# v5-pi.net
KiCad netlist of a schematic drawn in EAGLE
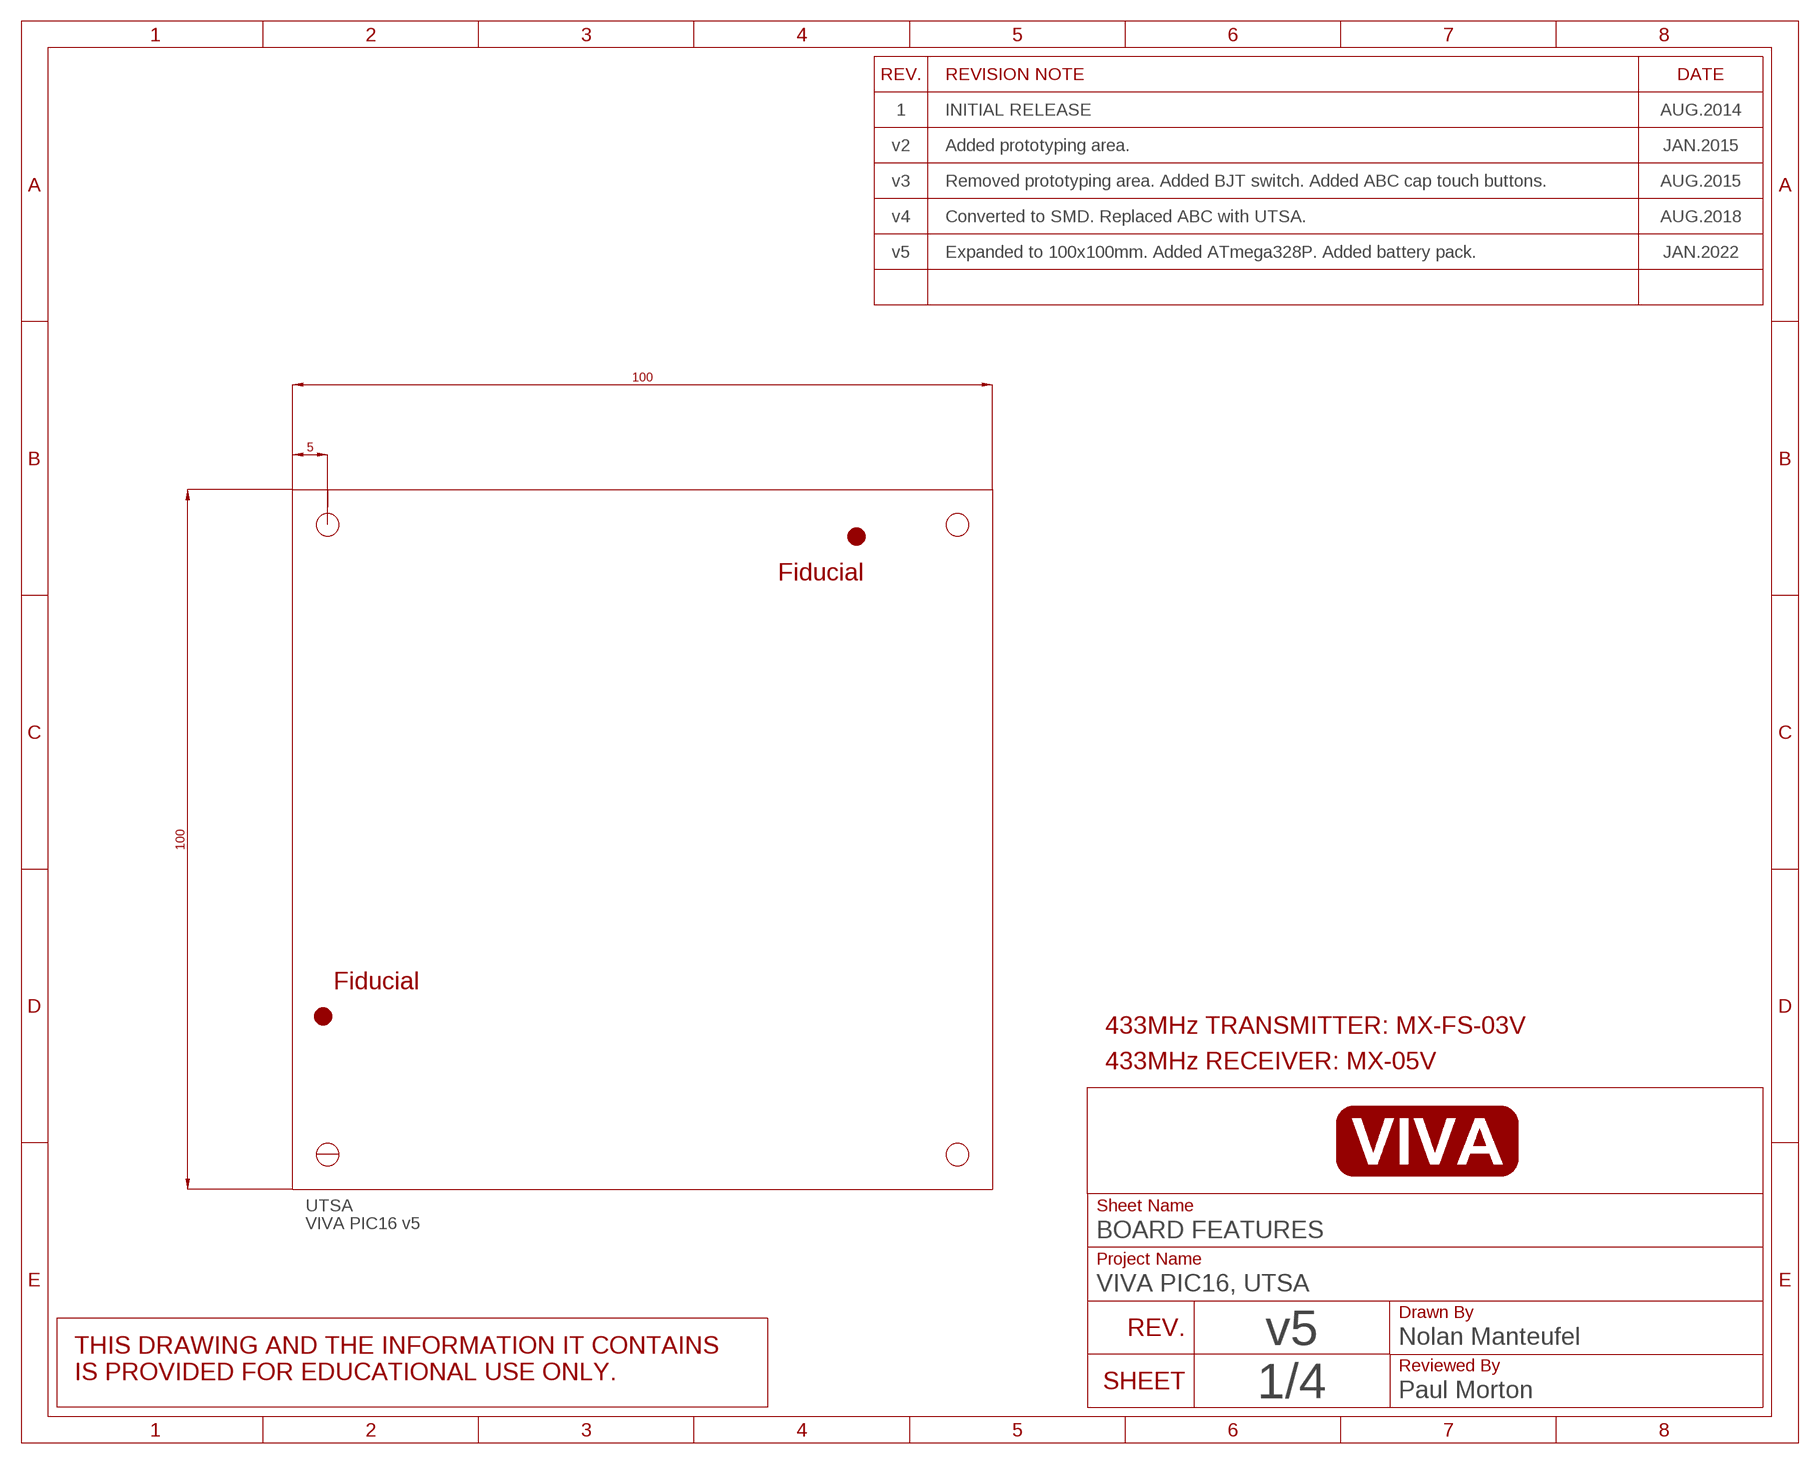
[diagram p0: schematic, sheet 1]
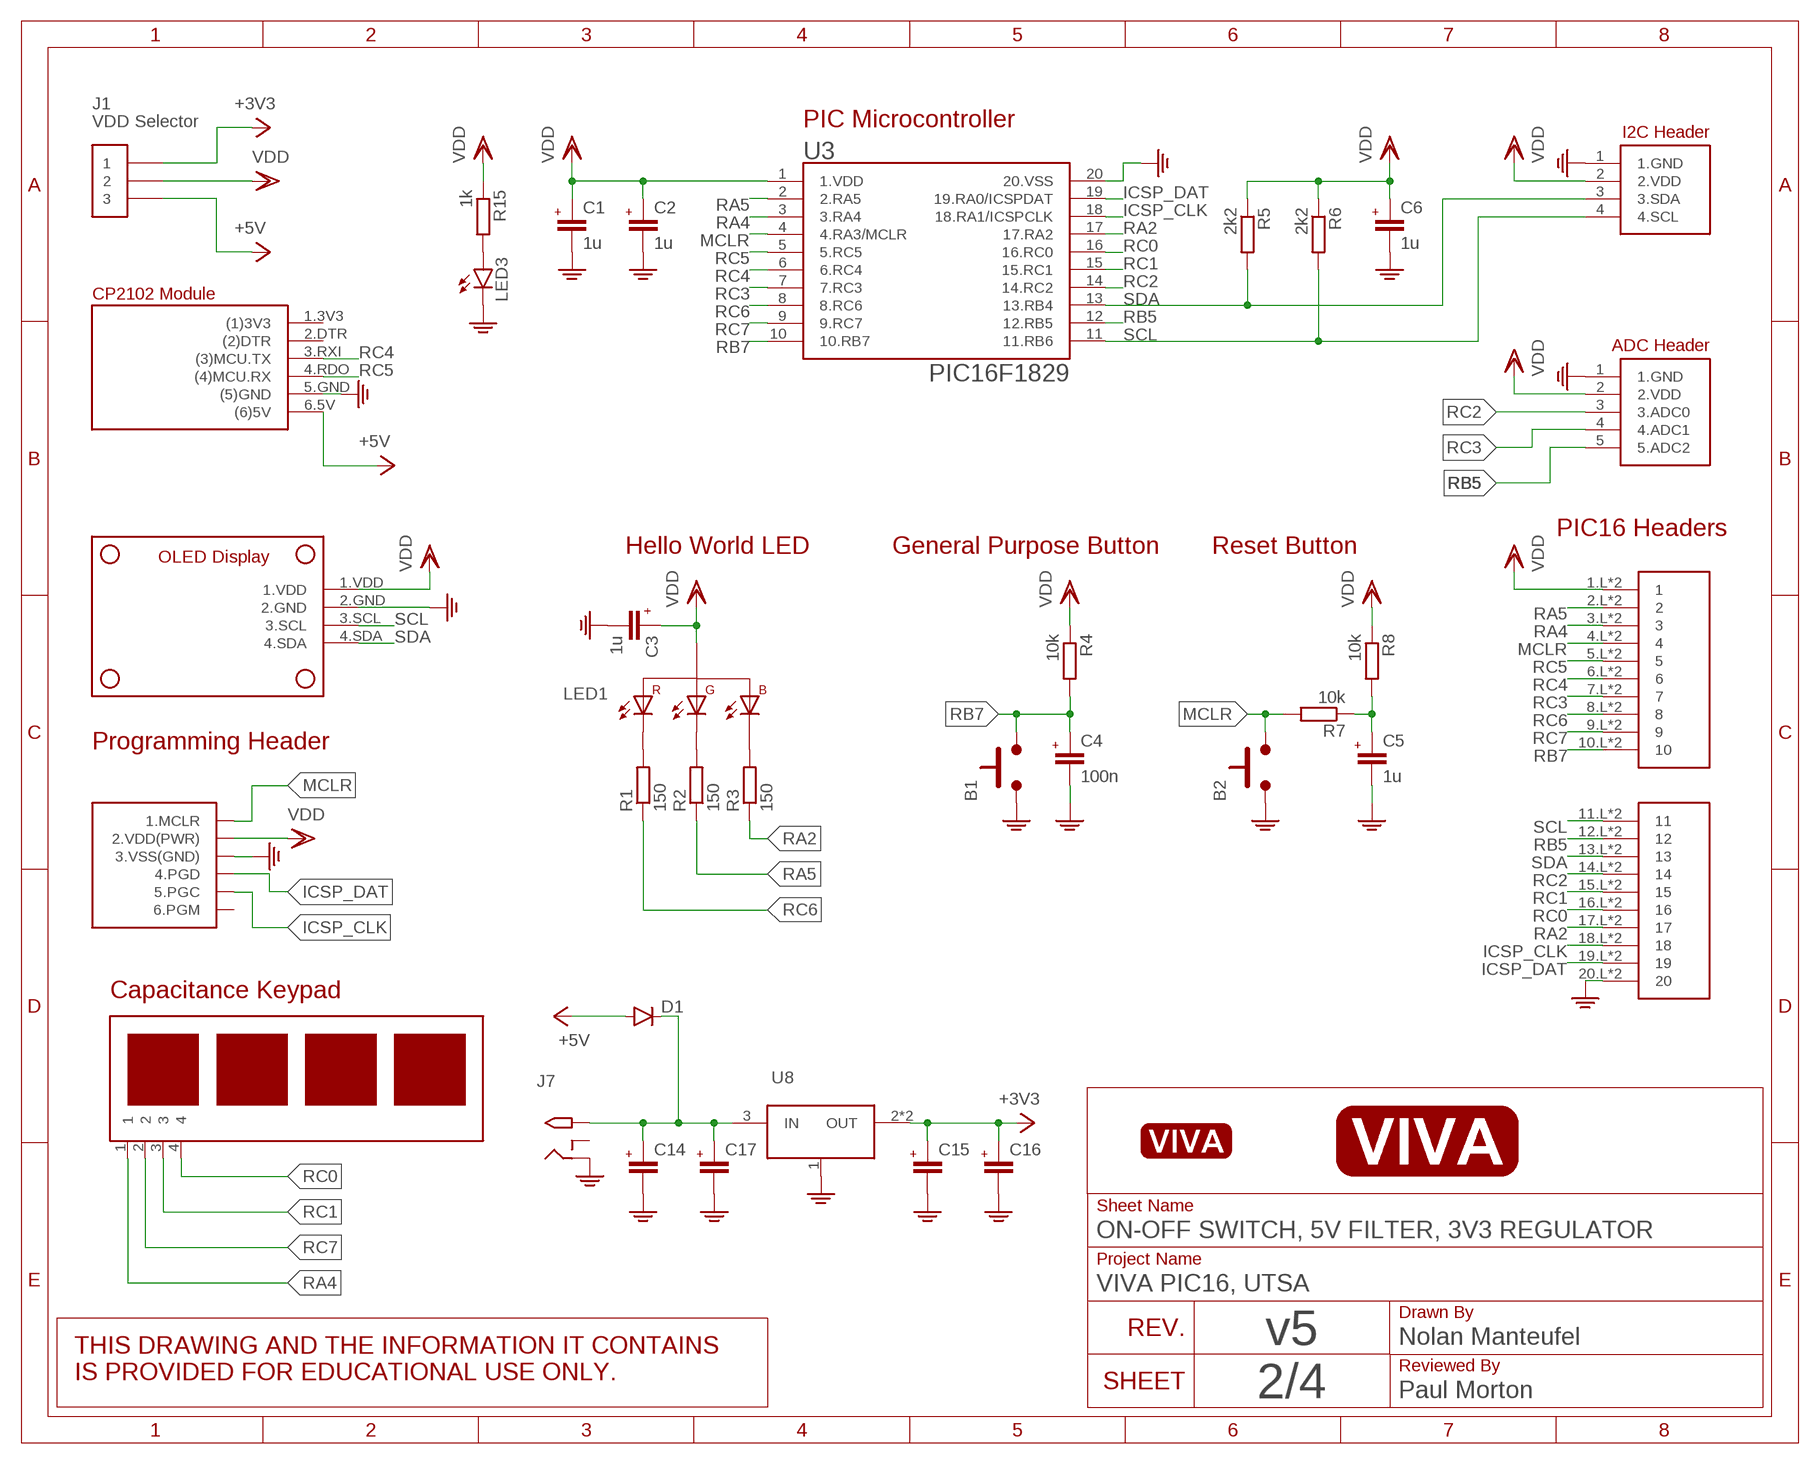
[diagram p1: schematic, sheet 2]
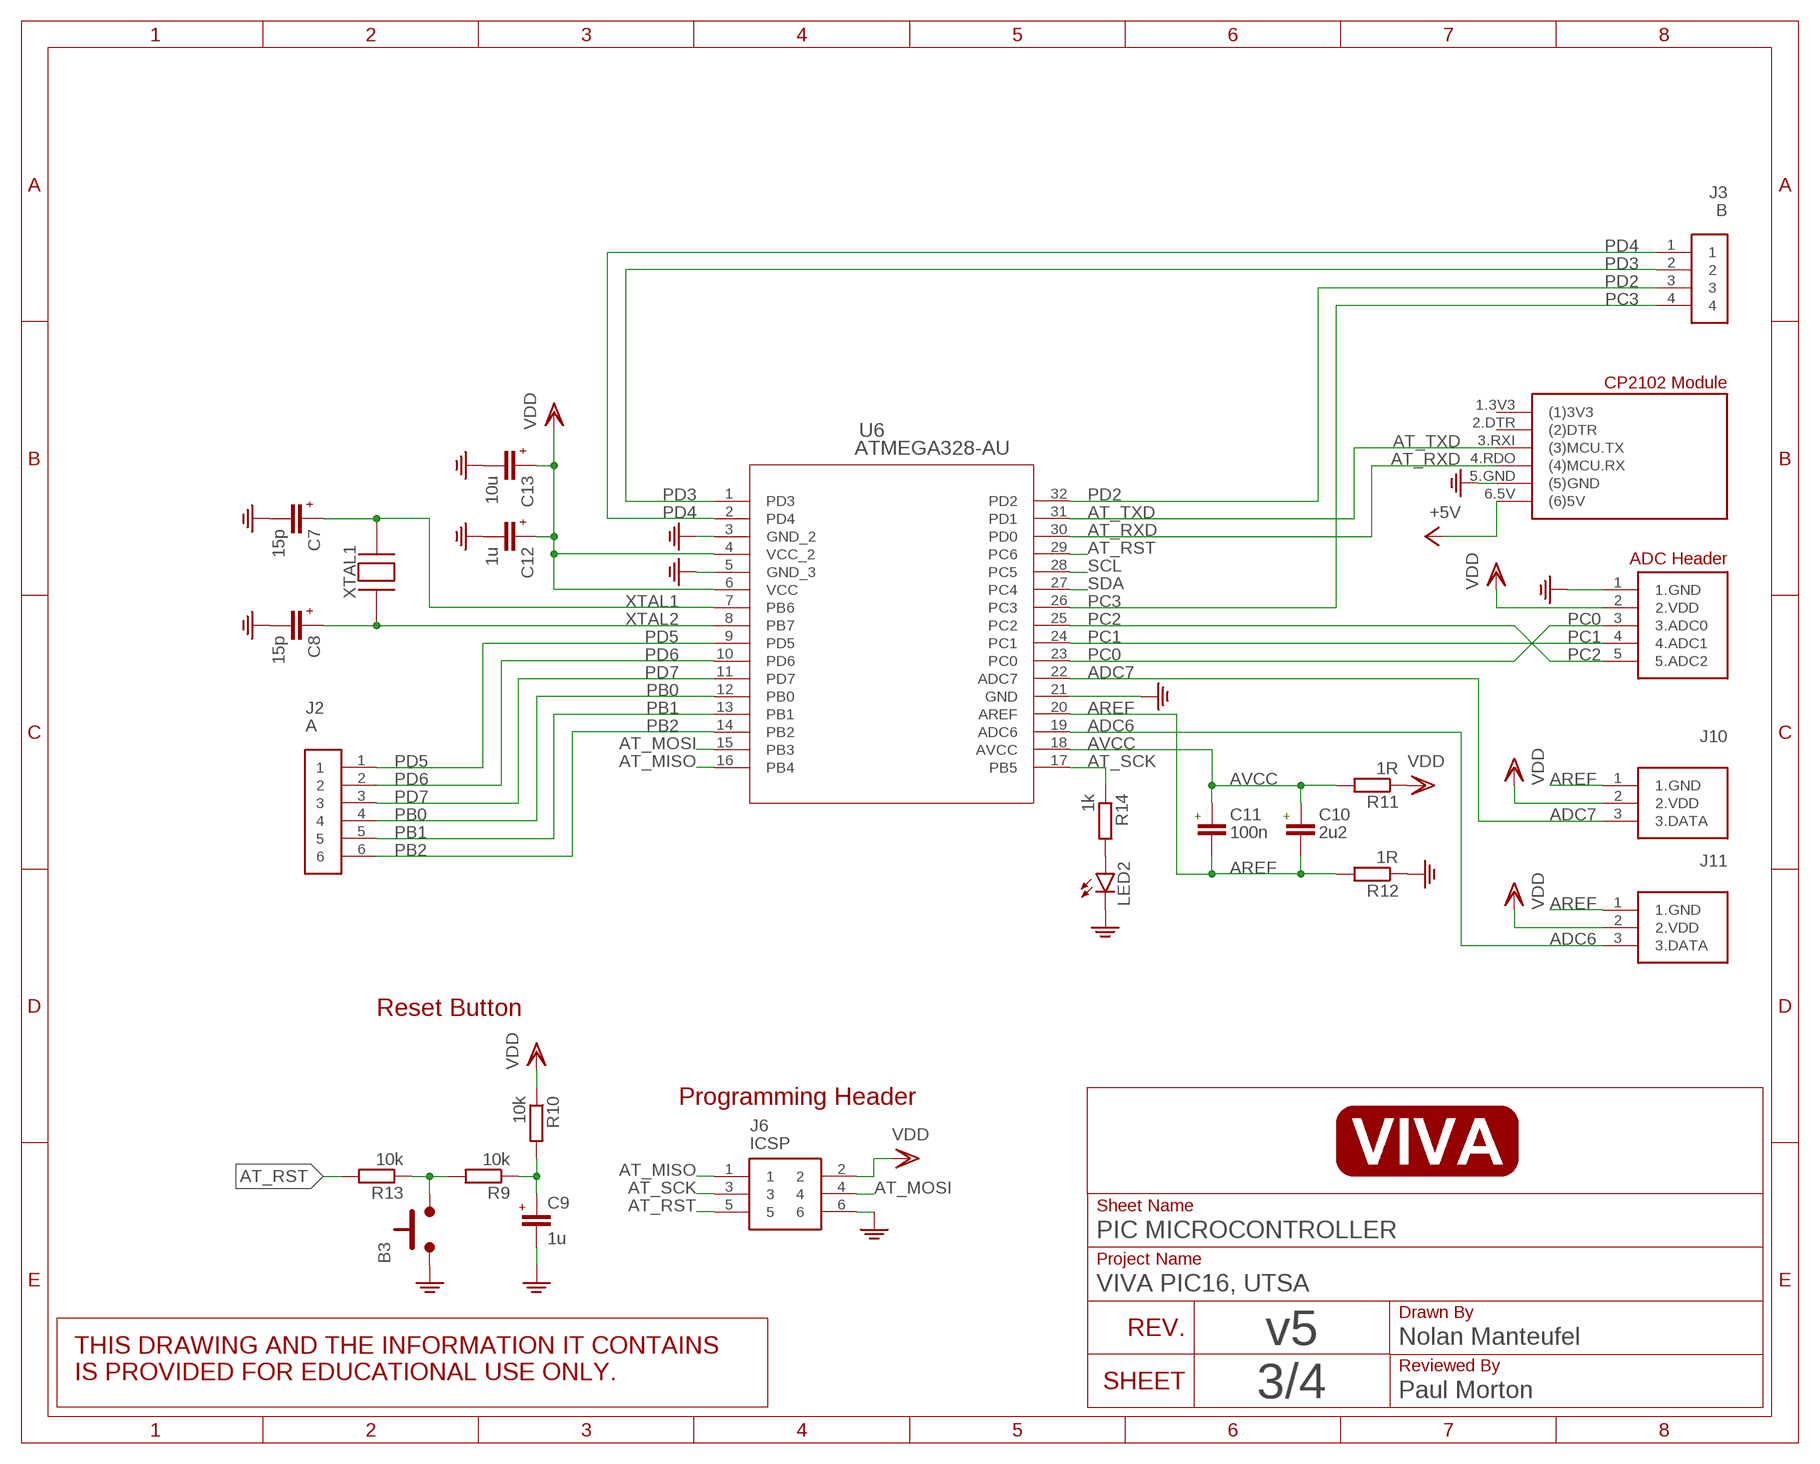
[diagram p2: schematic, sheet 3]
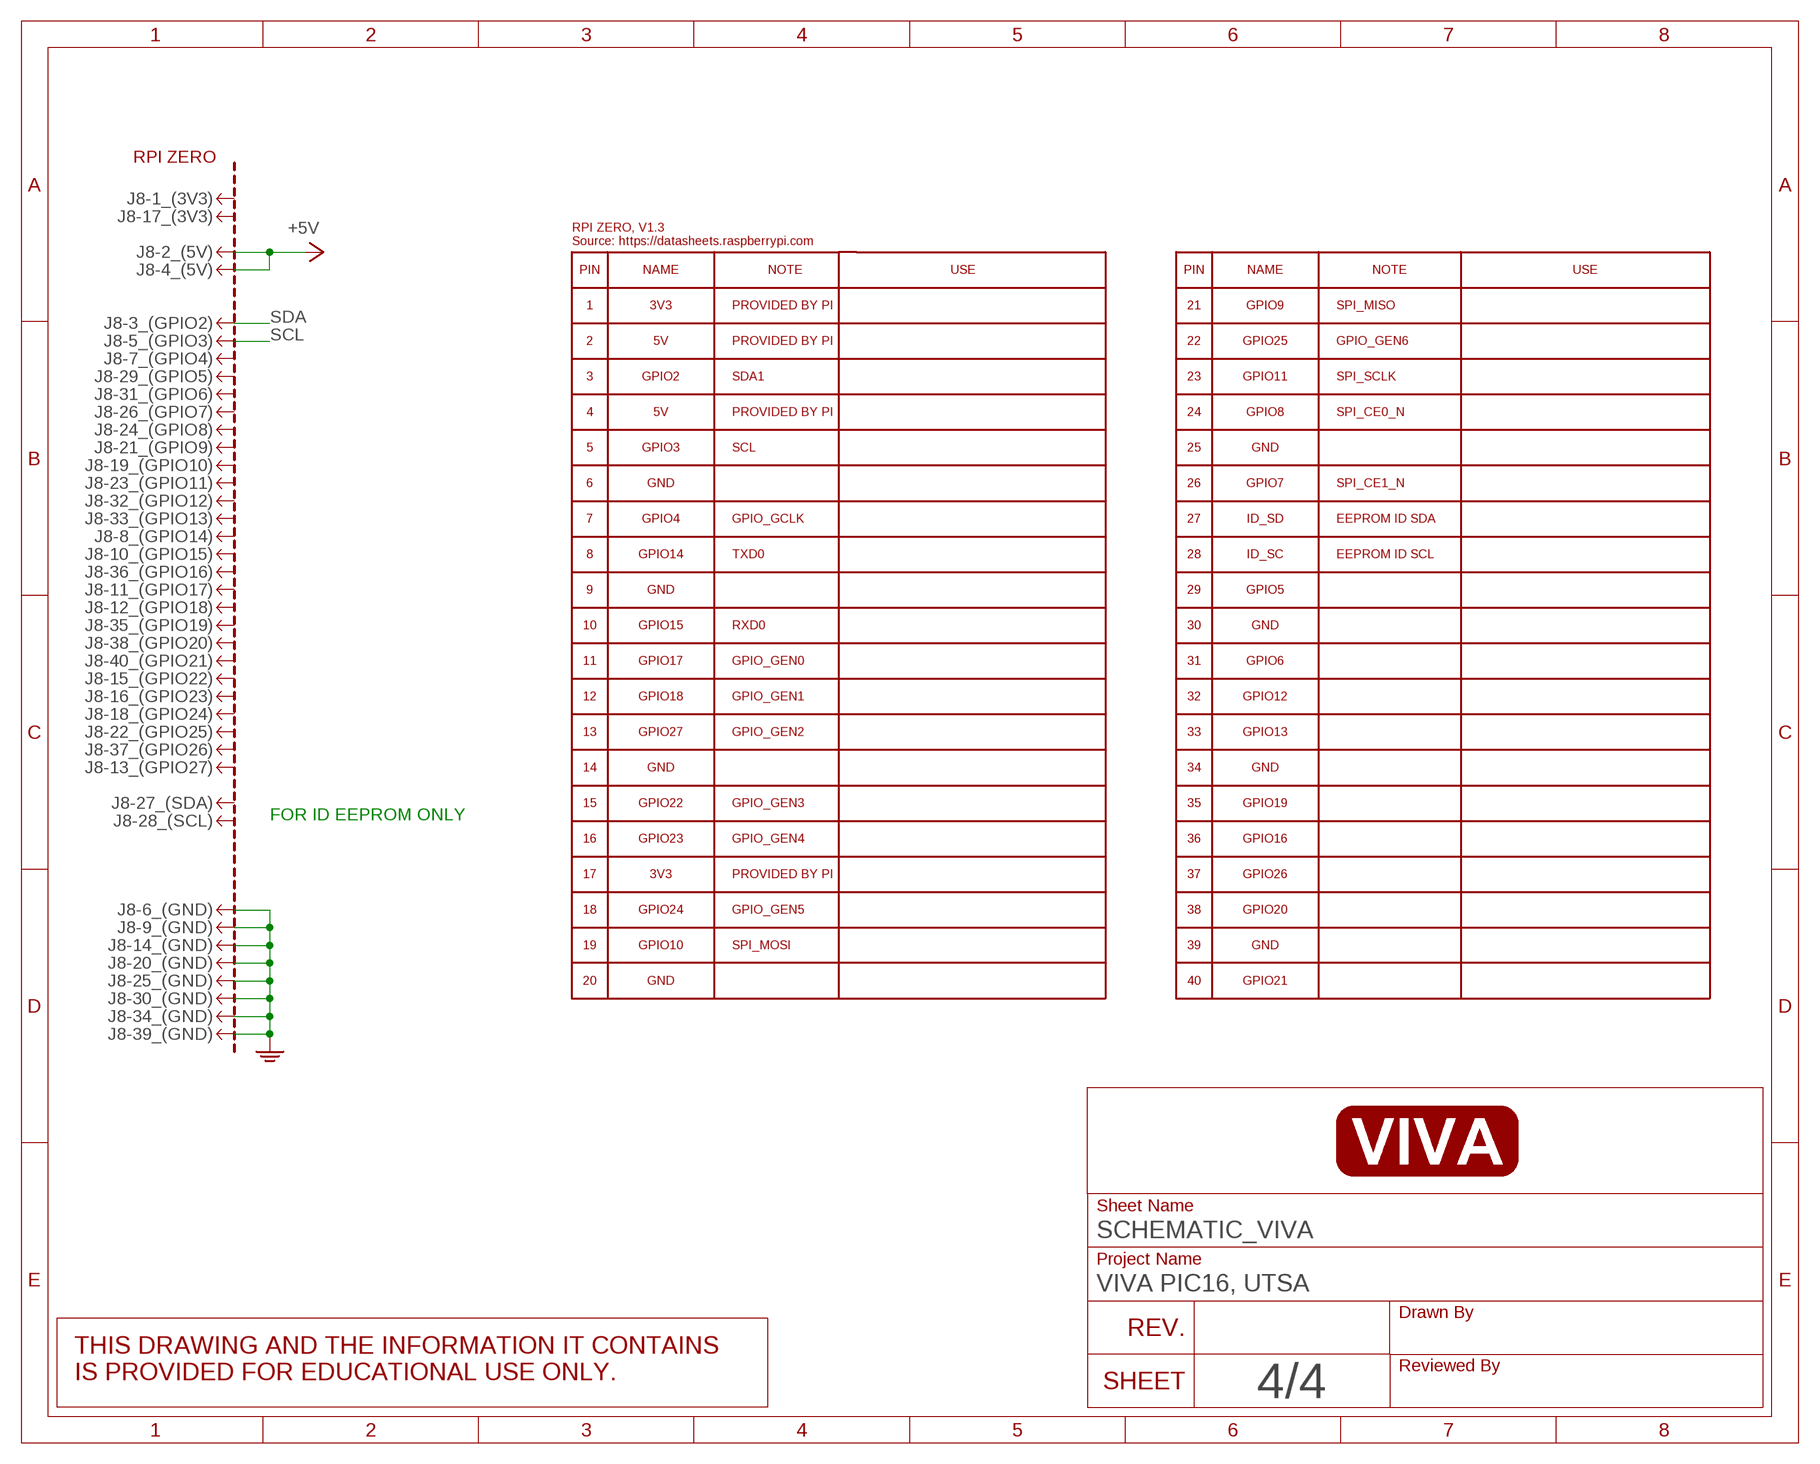
[diagram p3: schematic, sheet 4]

(export (version "E")
  (design (tool "Eeschema 10.0.6"))
  (components
    (comp (ref "B3")
      (value "PUSHBUTTON6X6MM")
      (footprint "eagle-import:6X6MM")
      (libsource (lib "eagle-import") (part "PUSHBUTTON6X6MM"))
    )
    (comp (ref "C7")
      (value "15p")
      (footprint "eagle-import:C0603")
      (libsource (lib "eagle-import") (part "C0603"))
    )
    (comp (ref "C8")
      (value "15p")
      (footprint "eagle-import:C0603")
      (libsource (lib "eagle-import") (part "C0603"))
    )
    (comp (ref "C9")
      (value "1u")
      (footprint "eagle-import:C0805")
      (libsource (lib "eagle-import") (part "C0805"))
    )
    (comp (ref "C10")
      (value "2u2")
      (footprint "eagle-import:C0805")
      (libsource (lib "eagle-import") (part "C-EU_C0805"))
    )
    (comp (ref "C11")
      (value "100n")
      (footprint "eagle-import:C0805")
      (libsource (lib "eagle-import") (part "C-EU_C0805"))
    )
    (comp (ref "C12")
      (value "1u")
      (footprint "eagle-import:C0805")
      (libsource (lib "eagle-import") (part "C0805"))
    )
    (comp (ref "C13")
      (value "10u")
      (footprint "eagle-import:C0805")
      (libsource (lib "eagle-import") (part "C0805"))
    )
    (comp (ref "J2")
      (value "A")
      (footprint "eagle-import:PINS_6")
      (libsource (lib "eagle-import") (part "PINS_6SQUARE"))
    )
    (comp (ref "J3")
      (value "B")
      (footprint "eagle-import:PINS_4")
      (libsource (lib "eagle-import") (part "PINS_4_0100"))
    )
    (comp (ref "J6")
      (value "ICSP")
      (footprint "eagle-import:PINS_6-2X3")
      (libsource (lib "eagle-import") (part "PINS_6-2X3"))
    )
    (comp (ref "J9")
      (value "VIVA-HEADER-ADC-PIC16")
      (footprint "eagle-import:VIVA-HEADER-ADC-PIC16")
      (libsource (lib "eagle-import") (part "VIVA-HEADER-ADC-PIC16"))
    )
    (comp (ref "J10")
      (value "VIVA-HEADER-GPIO-1")
      (footprint "eagle-import:VIVA-HEADER-GPIO-RA-1")
      (libsource (lib "eagle-import") (part "VIVA-HEADER-GPIO-1"))
    )
    (comp (ref "J11")
      (value "VIVA-HEADER-GPIO-1")
      (footprint "eagle-import:VIVA-HEADER-GPIO-RA-1")
      (libsource (lib "eagle-import") (part "VIVA-HEADER-GPIO-1"))
    )
    (comp (ref "LED2")
      (value "LEDSML0805")
      (footprint "eagle-import:SML0805")
      (libsource (lib "eagle-import") (part "LEDSML0805"))
    )
    (comp (ref "R9")
      (value "10k")
      (footprint "eagle-import:R0805")
      (libsource (lib "eagle-import") (part "R-EU__R0805"))
    )
    (comp (ref "R10")
      (value "10k")
      (footprint "eagle-import:R0805")
      (libsource (lib "eagle-import") (part "R-EU__R0805"))
    )
    (comp (ref "R11")
      (value "1R")
      (footprint "eagle-import:R0805")
      (libsource (lib "eagle-import") (part "R-EU__R0805"))
    )
    (comp (ref "R12")
      (value "1R")
      (footprint "eagle-import:R0805")
      (libsource (lib "eagle-import") (part "R-EU__R0805"))
    )
    (comp (ref "R13")
      (value "10k")
      (footprint "eagle-import:R0805")
      (libsource (lib "eagle-import") (part "R-EU__R0805"))
    )
    (comp (ref "R14")
      (value "1k")
      (footprint "eagle-import:R0805")
      (libsource (lib "eagle-import") (part "R-EU__R0805"))
    )
    (comp (ref "U6")
      (value "ATMEGA328-AU")
      (footprint "eagle-import:32A_ATM")
      (fields (field (name "COPYRIGHT") "Copyright (C) 2021 Ultra Librarian. All rights reserved."))
      (libsource (lib "eagle-import") (part "ATMEGA328-AU"))
    )
    (comp (ref "U7")
      (value "VIVA_USB-TTL")
      (footprint "eagle-import:VIVA_USB_TTL_SUBTEXT")
      (libsource (lib "eagle-import") (part "VIVA_USB-TTL"))
    )
    (comp (ref "XTAL1")
      (value "CRYSTAL-SMD")
      (footprint "eagle-import:HC49S-SMD")
      (libsource (lib "eagle-import") (part "CRYSTAL-SMD"))
    )
    (comp (ref "FIDUCIAL1")
      (value "FIDUCIAL")
      (footprint "eagle-import:FIDUCIAL")
      (libsource (lib "eagle-import") (part "FIDUCIAL"))
    )
    (comp (ref "FIDUCIAL2")
      (value "FIDUCIAL")
      (footprint "eagle-import:FIDUCIAL")
      (libsource (lib "eagle-import") (part "FIDUCIAL"))
    )
    (comp (ref "UTSA")
      (value "VIVA PIC16 v5")
      (footprint "eagle-import:PCB_100X100")
      (libsource (lib "eagle-import") (part "PCB_100X100"))
    )
    (comp (ref "B1")
      (value "PUSHBUTTON6X6MM")
      (footprint "eagle-import:6X6MM")
      (libsource (lib "eagle-import") (part "PUSHBUTTON6X6MM"))
    )
    (comp (ref "B2")
      (value "PUSHBUTTON6X6MM")
      (footprint "eagle-import:6X6MM")
      (libsource (lib "eagle-import") (part "PUSHBUTTON6X6MM"))
    )
    (comp (ref "C1")
      (value "1u")
      (footprint "eagle-import:C0805")
      (libsource (lib "eagle-import") (part "C0805"))
    )
    (comp (ref "C2")
      (value "1u")
      (footprint "eagle-import:C0805")
      (libsource (lib "eagle-import") (part "C0805"))
    )
    (comp (ref "C3")
      (value "1u")
      (footprint "eagle-import:C0805")
      (libsource (lib "eagle-import") (part "C0805"))
    )
    (comp (ref "C4")
      (value "100n")
      (footprint "eagle-import:C0805")
      (libsource (lib "eagle-import") (part "C0805"))
    )
    (comp (ref "C5")
      (value "1u")
      (footprint "eagle-import:C0805")
      (libsource (lib "eagle-import") (part "C0805"))
    )
    (comp (ref "C6")
      (value "1u")
      (footprint "eagle-import:C0805")
      (libsource (lib "eagle-import") (part "C0805"))
    )
    (comp (ref "C14")
      (value "C0805")
      (footprint "eagle-import:C0805")
      (libsource (lib "eagle-import") (part "C0805"))
    )
    (comp (ref "C15")
      (value "C0805")
      (footprint "eagle-import:C0805")
      (libsource (lib "eagle-import") (part "C0805"))
    )
    (comp (ref "C16")
      (value "C0805")
      (footprint "eagle-import:C0805")
      (libsource (lib "eagle-import") (part "C0805"))
    )
    (comp (ref "C17")
      (value "C0805")
      (footprint "eagle-import:C0805")
      (libsource (lib "eagle-import") (part "C0805"))
    )
    (comp (ref "D1")
      (value "DIODE-DO214AC")
      (footprint "eagle-import:DO214AC")
      (libsource (lib "eagle-import") (part "DIODE-DO214AC"))
    )
    (comp (ref "J1")
      (value "VDD Selector")
      (footprint "eagle-import:PINS_3")
      (libsource (lib "eagle-import") (part "PINS_3_2.54"))
    )
    (comp (ref "J4")
      (value "PICKIT3")
      (footprint "eagle-import:PICKIT3")
      (libsource (lib "eagle-import") (part "PICKIT3"))
    )
    (comp (ref "J5")
      (value "VIVA-HEADER-ADC-PIC16")
      (footprint "eagle-import:VIVA-HEADER-ADC-PIC16")
      (libsource (lib "eagle-import") (part "VIVA-HEADER-ADC-PIC16"))
    )
    (comp (ref "J7")
      (value "2.1MMJACKTHM")
      (footprint "eagle-import:PJ-102A")
      (libsource (lib "eagle-import") (part "2.1MMJACKTHM"))
    )
    (comp (ref "LED1")
      (value "LED_RGBLTST-C19FD1WT")
      (footprint "eagle-import:0805_RGB")
      (libsource (lib "eagle-import") (part "LED_RGBLTST-C19FD1WT"))
    )
    (comp (ref "LED3")
      (value "LEDSML0805")
      (footprint "eagle-import:SML0805")
      (libsource (lib "eagle-import") (part "LEDSML0805"))
    )
    (comp (ref "R1")
      (value "150")
      (footprint "eagle-import:R0805")
      (libsource (lib "eagle-import") (part "R-EU__R0805"))
    )
    (comp (ref "R2")
      (value "150")
      (footprint "eagle-import:R0805")
      (libsource (lib "eagle-import") (part "R-EU__R0805"))
    )
    (comp (ref "R3")
      (value "150")
      (footprint "eagle-import:R0805")
      (libsource (lib "eagle-import") (part "R-EU__R0805"))
    )
    (comp (ref "R4")
      (value "10k")
      (footprint "eagle-import:R0805")
      (libsource (lib "eagle-import") (part "R-EU__R0805"))
    )
    (comp (ref "R5")
      (value "2k2")
      (footprint "eagle-import:R0805")
      (libsource (lib "eagle-import") (part "R-EU__R0805"))
    )
    (comp (ref "R6")
      (value "2k2")
      (footprint "eagle-import:R0805")
      (libsource (lib "eagle-import") (part "R-EU__R0805"))
    )
    (comp (ref "R7")
      (value "10k")
      (footprint "eagle-import:R0805")
      (libsource (lib "eagle-import") (part "R-EU__R0805"))
    )
    (comp (ref "R8")
      (value "10k")
      (footprint "eagle-import:R0805")
      (libsource (lib "eagle-import") (part "R-EU__R0805"))
    )
    (comp (ref "R15")
      (value "1k")
      (footprint "eagle-import:R0805")
      (libsource (lib "eagle-import") (part "R-EU__R0805"))
    )
    (comp (ref "U$2")
      (value "VIVA_LOGO")
      (footprint "eagle-import:VIVA_LOGO")
      (libsource (lib "eagle-import") (part "VIVA_LOGO"))
    )
    (comp (ref "U$3")
      (value "VIVA_OLED")
      (footprint "eagle-import:VIVA_OLED-I2C")
      (libsource (lib "eagle-import") (part "VIVA_OLED"))
    )
    (comp (ref "U1")
      (value "VIVA_UTSA-KEYPADV5")
      (footprint "eagle-import:VIVA_UTSA-KEYPAD-V5")
      (libsource (lib "eagle-import") (part "VIVA_UTSA-KEYPADV5"))
    )
    (comp (ref "U2")
      (value "VIVA_USB-TTL")
      (footprint "eagle-import:VIVA_USB_TTL_SUBTEXT")
      (libsource (lib "eagle-import") (part "VIVA_USB-TTL"))
    )
    (comp (ref "U3")
      (value "PIC16F1829")
      (footprint "eagle-import:SOP20-NEW")
      (libsource (lib "eagle-import") (part "PIC16F1829300"))
    )
    (comp (ref "U4")
      (value "VIVA-HEADER-I2C-RA")
      (footprint "eagle-import:VIVA-HEADER-I2C-RA")
      (libsource (lib "eagle-import") (part "VIVA-HEADER-I2C-RA"))
    )
    (comp (ref "U5")
      (value "VIVA_PIC16BOARD")
      (footprint "eagle-import:VIVA_PIC16")
      (libsource (lib "eagle-import") (part "VIVA_PIC16BOARD"))
    )
    (comp (ref "U8")
      (value "REGULATOR_SCHLM1117")
      (footprint "eagle-import:SOT223")
      (libsource (lib "eagle-import") (part "REGULATOR_SCHLM1117"))
    )
    (comp (ref "J8-")
      (value "RPI ZERO")
      (footprint "eagle-import:RPI_ZERO")
      (libsource (lib "eagle-import") (part "RPI_ZERO"))
    )
  )
  (nets
    (net (code "1") (name "+3V3") (class "Default")
      (node (ref "C15") (pin "2") (pinfunction "+_2") (pintype "passive"))
      (node (ref "C16") (pin "2") (pinfunction "+_2") (pintype "passive"))
      (node (ref "J1") (pin "1") (pinfunction "1_1") (pintype "bidirectional"))
      (node (ref "U8") (pin "2") (pinfunction "OUT_2") (pintype "bidirectional"))
      (node (ref "U8") (pin "4.TAB") (pinfunction "OUT_4.TAB") (pintype "bidirectional"))
    )
    (net (code "2") (name "+5V") (class "Default")
      (node (ref "D1") (pin "A") (pinfunction "A_A") (pintype "passive"))
      (node (ref "J1") (pin "3") (pinfunction "3_3") (pintype "bidirectional"))
      (node (ref "J8-") (pin "2") (pinfunction "1_2") (pintype "bidirectional"))
      (node (ref "J8-") (pin "4") (pinfunction "1_4") (pintype "bidirectional"))
      (node (ref "U2") (pin "6.5V") (pinfunction "(6)5V_6.5V") (pintype "bidirectional"))
      (node (ref "U7") (pin "6.5V") (pinfunction "(6)5V_6.5V") (pintype "bidirectional"))
    )
    (net (code "3") (name "ADC6") (class "Default")
      (node (ref "J11") (pin "3") (pinfunction "3.DATA_3") (pintype "bidirectional"))
      (node (ref "U6") (pin "19") (pinfunction "ADC6_19") (pintype "passive"))
    )
    (net (code "4") (name "ADC7") (class "Default")
      (node (ref "J10") (pin "3") (pinfunction "3.DATA_3") (pintype "bidirectional"))
      (node (ref "U6") (pin "22") (pinfunction "ADC7_22") (pintype "passive"))
    )
    (net (code "5") (name "AREF") (class "Default")
      (node (ref "C10") (pin "2") (pinfunction "2_2") (pintype "passive"))
      (node (ref "C11") (pin "2") (pinfunction "2_2") (pintype "passive"))
      (node (ref "J10") (pin "1") (pinfunction "1.GND_1") (pintype "bidirectional"))
      (node (ref "J11") (pin "1") (pinfunction "1.GND_1") (pintype "bidirectional"))
      (node (ref "R12") (pin "2") (pinfunction "2_2") (pintype "passive"))
      (node (ref "U6") (pin "20") (pinfunction "AREF_20") (pintype "passive"))
    )
    (net (code "6") (name "AT_MISO") (class "Default")
      (node (ref "J6") (pin "1") (pinfunction "1_1") (pintype "bidirectional"))
      (node (ref "U6") (pin "16") (pinfunction "PB4_16") (pintype "bidirectional"))
    )
    (net (code "7") (name "AT_MOSI") (class "Default")
      (node (ref "J6") (pin "4") (pinfunction "4_4") (pintype "bidirectional"))
      (node (ref "U6") (pin "15") (pinfunction "PB3_15") (pintype "bidirectional"))
    )
    (net (code "8") (name "AT_RST") (class "Default")
      (node (ref "J6") (pin "5") (pinfunction "5_5") (pintype "bidirectional"))
      (node (ref "R13") (pin "2") (pinfunction "2_2") (pintype "passive"))
      (node (ref "U6") (pin "29") (pinfunction "PC6_29") (pintype "bidirectional"))
    )
    (net (code "9") (name "AT_RXD") (class "Default")
      (node (ref "U6") (pin "30") (pinfunction "PD0_30") (pintype "bidirectional"))
      (node (ref "U7") (pin "4.RDO") (pinfunction "(4)MCU.RX_4.RDO") (pintype "bidirectional"))
    )
    (net (code "10") (name "AT_SCK") (class "Default")
      (node (ref "J6") (pin "3") (pinfunction "3_3") (pintype "bidirectional"))
      (node (ref "R14") (pin "1") (pinfunction "1_1") (pintype "passive"))
      (node (ref "U6") (pin "17") (pinfunction "PB5_17") (pintype "bidirectional"))
    )
    (net (code "11") (name "AT_TXD") (class "Default")
      (node (ref "U6") (pin "31") (pinfunction "PD1_31") (pintype "bidirectional"))
      (node (ref "U7") (pin "3.RXI") (pinfunction "(3)MCU.TX_3.RXI") (pintype "bidirectional"))
    )
    (net (code "12") (name "AVCC") (class "Default")
      (node (ref "C10") (pin "1") (pinfunction "1_1") (pintype "passive"))
      (node (ref "C11") (pin "1") (pinfunction "1_1") (pintype "passive"))
      (node (ref "R11") (pin "2") (pinfunction "2_2") (pintype "passive"))
      (node (ref "U6") (pin "18") (pinfunction "AVCC_18") (pintype "power_in"))
    )
    (net (code "13") (name "GND") (class "Default")
      (node (ref "B1") (pin "1.A") (pinfunction "1_1.A") (pintype "bidirectional"))
      (node (ref "B1") (pin "2.A") (pinfunction "1_2.A") (pintype "bidirectional"))
      (node (ref "B2") (pin "1.A") (pinfunction "1_1.A") (pintype "bidirectional"))
      (node (ref "B2") (pin "2.A") (pinfunction "1_2.A") (pintype "bidirectional"))
      (node (ref "B3") (pin "1.A") (pinfunction "1_1.A") (pintype "bidirectional"))
      (node (ref "B3") (pin "2.A") (pinfunction "1_2.A") (pintype "bidirectional"))
      (node (ref "C1") (pin "1") (pinfunction "-_1") (pintype "passive"))
      (node (ref "C12") (pin "1") (pinfunction "-_1") (pintype "passive"))
      (node (ref "C13") (pin "1") (pinfunction "-_1") (pintype "passive"))
      (node (ref "C14") (pin "1") (pinfunction "-_1") (pintype "passive"))
      (node (ref "C15") (pin "1") (pinfunction "-_1") (pintype "passive"))
      (node (ref "C16") (pin "1") (pinfunction "-_1") (pintype "passive"))
      (node (ref "C17") (pin "1") (pinfunction "-_1") (pintype "passive"))
      (node (ref "C2") (pin "1") (pinfunction "-_1") (pintype "passive"))
      (node (ref "C3") (pin "1") (pinfunction "-_1") (pintype "passive"))
      (node (ref "C4") (pin "1") (pinfunction "-_1") (pintype "passive"))
      (node (ref "C5") (pin "1") (pinfunction "-_1") (pintype "passive"))
      (node (ref "C6") (pin "1") (pinfunction "-_1") (pintype "passive"))
      (node (ref "C7") (pin "1") (pinfunction "-_1") (pintype "passive"))
      (node (ref "C8") (pin "1") (pinfunction "-_1") (pintype "passive"))
      (node (ref "C9") (pin "1") (pinfunction "-_1") (pintype "passive"))
      (node (ref "J4") (pin "3") (pinfunction "3.VSS(GND)_3") (pintype "bidirectional"))
      (node (ref "J5") (pin "1") (pinfunction "1.GND_1") (pintype "bidirectional"))
      (node (ref "J6") (pin "6") (pinfunction "6_6") (pintype "bidirectional"))
      (node (ref "J7") (pin "RING") (pinfunction "RING_RING") (pintype "bidirectional"))
      (node (ref "J8-") (pin "14") (pinfunction "1_14") (pintype "bidirectional"))
      (node (ref "J8-") (pin "20") (pinfunction "1_20") (pintype "bidirectional"))
      (node (ref "J8-") (pin "25") (pinfunction "1_25") (pintype "bidirectional"))
      (node (ref "J8-") (pin "30") (pinfunction "1_30") (pintype "bidirectional"))
      (node (ref "J8-") (pin "34") (pinfunction "1_34") (pintype "bidirectional"))
      (node (ref "J8-") (pin "39") (pinfunction "1_39") (pintype "bidirectional"))
      (node (ref "J8-") (pin "6") (pinfunction "1_6") (pintype "bidirectional"))
      (node (ref "J8-") (pin "9") (pinfunction "1_9") (pintype "bidirectional"))
      (node (ref "J9") (pin "1") (pinfunction "1.GND_1") (pintype "bidirectional"))
      (node (ref "LED2") (pin "C") (pinfunction "C_C") (pintype "passive"))
      (node (ref "LED3") (pin "C") (pinfunction "C_C") (pintype "passive"))
      (node (ref "R12") (pin "1") (pinfunction "1_1") (pintype "passive"))
      (node (ref "U$3") (pin "2.GND") (pinfunction "2.GND_2.GND") (pintype "bidirectional"))
      (node (ref "U2") (pin "5.GND") (pinfunction "(5)GND_5.GND") (pintype "bidirectional"))
      (node (ref "U3") (pin "20") (pinfunction "20.VSS_20") (pintype "bidirectional"))
      (node (ref "U4") (pin "1") (pinfunction "1.GND_1") (pintype "bidirectional"))
      (node (ref "U5") (pin "20.L") (pinfunction "20_20.L") (pintype "bidirectional"))
      (node (ref "U5") (pin "20.R") (pinfunction "20_20.R") (pintype "bidirectional"))
      (node (ref "U6") (pin "21") (pinfunction "GND_21") (pintype "power_in"))
      (node (ref "U6") (pin "3") (pinfunction "GND_2_3") (pintype "power_in"))
      (node (ref "U6") (pin "5") (pinfunction "GND_3_5") (pintype "power_in"))
      (node (ref "U7") (pin "5.GND") (pinfunction "(5)GND_5.GND") (pintype "bidirectional"))
      (node (ref "U8") (pin "1") (pinfunction "GND_1") (pintype "bidirectional"))
    )
    (net (code "14") (name "ICSP_CLK") (class "Default")
      (node (ref "J4") (pin "5") (pinfunction "5.PGC_5") (pintype "bidirectional"))
      (node (ref "U3") (pin "18") (pinfunction "18.RA1/ICSPCLK_18") (pintype "bidirectional"))
      (node (ref "U5") (pin "18.L") (pinfunction "18_18.L") (pintype "bidirectional"))
      (node (ref "U5") (pin "18.R") (pinfunction "18_18.R") (pintype "bidirectional"))
    )
    (net (code "15") (name "ICSP_DAT") (class "Default")
      (node (ref "J4") (pin "4") (pinfunction "4.PGD_4") (pintype "bidirectional"))
      (node (ref "U3") (pin "19") (pinfunction "19.RA0/ICSPDAT_19") (pintype "bidirectional"))
      (node (ref "U5") (pin "19.L") (pinfunction "19_19.L") (pintype "bidirectional"))
      (node (ref "U5") (pin "19.R") (pinfunction "19_19.R") (pintype "bidirectional"))
    )
    (net (code "16") (name "MCLR") (class "Default")
      (node (ref "B2") (pin "3.B") (pinfunction "2_3.B") (pintype "bidirectional"))
      (node (ref "B2") (pin "4.B") (pinfunction "2_4.B") (pintype "bidirectional"))
      (node (ref "J4") (pin "1") (pinfunction "1.MCLR_1") (pintype "bidirectional"))
      (node (ref "R7") (pin "2") (pinfunction "2_2") (pintype "passive"))
      (node (ref "U3") (pin "4") (pinfunction "4.RA3/MCLR_4") (pintype "bidirectional"))
      (node (ref "U5") (pin "4.L") (pinfunction "4_4.L") (pintype "bidirectional"))
      (node (ref "U5") (pin "4.R") (pinfunction "4_4.R") (pintype "bidirectional"))
    )
    (net (code "17") (name "Net-(B3-2-Pad3.B)") (class "Default")
      (node (ref "B3") (pin "3.B") (pinfunction "2_3.B") (pintype "bidirectional"))
      (node (ref "B3") (pin "4.B") (pinfunction "2_4.B") (pintype "bidirectional"))
      (node (ref "R13") (pin "1") (pinfunction "1_1") (pintype "passive"))
      (node (ref "R9") (pin "2") (pinfunction "2_2") (pintype "passive"))
    )
    (net (code "18") (name "Net-(C5-+)") (class "Default")
      (node (ref "C5") (pin "2") (pinfunction "+_2") (pintype "passive"))
      (node (ref "R7") (pin "1") (pinfunction "1_1") (pintype "passive"))
      (node (ref "R8") (pin "2") (pinfunction "2_2") (pintype "passive"))
    )
    (net (code "19") (name "Net-(C9-+)") (class "Default")
      (node (ref "C9") (pin "2") (pinfunction "+_2") (pintype "passive"))
      (node (ref "R10") (pin "2") (pinfunction "2_2") (pintype "passive"))
      (node (ref "R9") (pin "1") (pinfunction "1_1") (pintype "passive"))
    )
    (net (code "20") (name "Net-(C14-+)") (class "Default")
      (node (ref "C14") (pin "2") (pinfunction "+_2") (pintype "passive"))
      (node (ref "C17") (pin "2") (pinfunction "+_2") (pintype "passive"))
      (node (ref "D1") (pin "C") (pinfunction "C_C") (pintype "passive"))
      (node (ref "J7") (pin "TIP") (pinfunction "TIP_TIP") (pintype "bidirectional"))
      (node (ref "U8") (pin "3") (pinfunction "IN_3") (pintype "bidirectional"))
    )
    (net (code "21") (name "Net-(LED1-1.R-)") (class "Default")
      (node (ref "LED1") (pin "2") (pinfunction "1.R-_2") (pintype "passive"))
      (node (ref "R1") (pin "2") (pinfunction "2_2") (pintype "passive"))
    )
    (net (code "22") (name "Net-(LED1-2.G-)") (class "Default")
      (node (ref "LED1") (pin "3") (pinfunction "2.G-_3") (pintype "passive"))
      (node (ref "R2") (pin "2") (pinfunction "2_2") (pintype "passive"))
    )
    (net (code "23") (name "Net-(LED1-4.B-)") (class "Default")
      (node (ref "LED1") (pin "1") (pinfunction "4.B-_1") (pintype "passive"))
      (node (ref "R3") (pin "2") (pinfunction "2_2") (pintype "passive"))
    )
    (net (code "24") (name "Net-(LED2-PadA)") (class "Default")
      (node (ref "LED2") (pin "A") (pinfunction "A_A") (pintype "passive"))
      (node (ref "R14") (pin "2") (pinfunction "2_2") (pintype "passive"))
    )
    (net (code "25") (name "Net-(LED3-PadA)") (class "Default")
      (node (ref "LED3") (pin "A") (pinfunction "A_A") (pintype "passive"))
      (node (ref "R15") (pin "2") (pinfunction "2_2") (pintype "passive"))
    )
    (net (code "26") (name "PB0") (class "Default")
      (node (ref "J2") (pin "4") (pinfunction "4_4") (pintype "bidirectional"))
      (node (ref "U6") (pin "12") (pinfunction "PB0_12") (pintype "bidirectional"))
    )
    (net (code "27") (name "PB1") (class "Default")
      (node (ref "J2") (pin "5") (pinfunction "5_5") (pintype "bidirectional"))
      (node (ref "U6") (pin "13") (pinfunction "PB1_13") (pintype "bidirectional"))
    )
    (net (code "28") (name "PB2") (class "Default")
      (node (ref "J2") (pin "6") (pinfunction "6_6") (pintype "bidirectional"))
      (node (ref "U6") (pin "14") (pinfunction "PB2_14") (pintype "bidirectional"))
    )
    (net (code "29") (name "PC0") (class "Default")
      (node (ref "J9") (pin "3") (pinfunction "3.ADC0_3") (pintype "bidirectional"))
      (node (ref "U6") (pin "23") (pinfunction "PC0_23") (pintype "bidirectional"))
    )
    (net (code "30") (name "PC1") (class "Default")
      (node (ref "J9") (pin "4") (pinfunction "4.ADC1_4") (pintype "bidirectional"))
      (node (ref "U6") (pin "24") (pinfunction "PC1_24") (pintype "bidirectional"))
    )
    (net (code "31") (name "PC2") (class "Default")
      (node (ref "J9") (pin "5") (pinfunction "5.ADC2_5") (pintype "bidirectional"))
      (node (ref "U6") (pin "25") (pinfunction "PC2_25") (pintype "bidirectional"))
    )
    (net (code "32") (name "PC3") (class "Default")
      (node (ref "J3") (pin "4") (pinfunction "4_4") (pintype "bidirectional"))
      (node (ref "U6") (pin "26") (pinfunction "PC3_26") (pintype "bidirectional"))
    )
    (net (code "33") (name "PD2") (class "Default")
      (node (ref "J3") (pin "3") (pinfunction "3_3") (pintype "bidirectional"))
      (node (ref "U6") (pin "32") (pinfunction "PD2_32") (pintype "bidirectional"))
    )
    (net (code "34") (name "PD3") (class "Default")
      (node (ref "J3") (pin "2") (pinfunction "2_2") (pintype "bidirectional"))
      (node (ref "U6") (pin "1") (pinfunction "PD3_1") (pintype "bidirectional"))
    )
    (net (code "35") (name "PD4") (class "Default")
      (node (ref "J3") (pin "1") (pinfunction "1_1") (pintype "bidirectional"))
      (node (ref "U6") (pin "2") (pinfunction "PD4_2") (pintype "bidirectional"))
    )
    (net (code "36") (name "PD5") (class "Default")
      (node (ref "J2") (pin "1") (pinfunction "1_1") (pintype "bidirectional"))
      (node (ref "U6") (pin "9") (pinfunction "PD5_9") (pintype "bidirectional"))
    )
    (net (code "37") (name "PD6") (class "Default")
      (node (ref "J2") (pin "2") (pinfunction "2_2") (pintype "bidirectional"))
      (node (ref "U6") (pin "10") (pinfunction "PD6_10") (pintype "bidirectional"))
    )
    (net (code "38") (name "PD7") (class "Default")
      (node (ref "J2") (pin "3") (pinfunction "3_3") (pintype "bidirectional"))
      (node (ref "U6") (pin "11") (pinfunction "PD7_11") (pintype "bidirectional"))
    )
    (net (code "39") (name "RA2") (class "Default")
      (node (ref "R3") (pin "1") (pinfunction "1_1") (pintype "passive"))
      (node (ref "U3") (pin "17") (pinfunction "17.RA2_17") (pintype "bidirectional"))
      (node (ref "U5") (pin "17.L") (pinfunction "17_17.L") (pintype "bidirectional"))
      (node (ref "U5") (pin "17.R") (pinfunction "17_17.R") (pintype "bidirectional"))
    )
    (net (code "40") (name "RA4") (class "Default")
      (node (ref "U1") (pin "1") (pinfunction "1_1") (pintype "bidirectional"))
      (node (ref "U3") (pin "3") (pinfunction "3.RA4_3") (pintype "bidirectional"))
      (node (ref "U5") (pin "3.L") (pinfunction "3_3.L") (pintype "bidirectional"))
      (node (ref "U5") (pin "3.R") (pinfunction "3_3.R") (pintype "bidirectional"))
    )
    (net (code "41") (name "RA5") (class "Default")
      (node (ref "R2") (pin "1") (pinfunction "1_1") (pintype "passive"))
      (node (ref "U3") (pin "2") (pinfunction "2.RA5_2") (pintype "bidirectional"))
      (node (ref "U5") (pin "2.L") (pinfunction "2_2.L") (pintype "bidirectional"))
      (node (ref "U5") (pin "2.R") (pinfunction "2_2.R") (pintype "bidirectional"))
    )
    (net (code "42") (name "RB5") (class "Default")
      (node (ref "J5") (pin "5") (pinfunction "5.ADC2_5") (pintype "bidirectional"))
      (node (ref "U3") (pin "12") (pinfunction "12.RB5_12") (pintype "bidirectional"))
      (node (ref "U5") (pin "12.L") (pinfunction "12_12.L") (pintype "bidirectional"))
      (node (ref "U5") (pin "12.R") (pinfunction "12_12.R") (pintype "bidirectional"))
    )
    (net (code "43") (name "RB7") (class "Default")
      (node (ref "B1") (pin "3.B") (pinfunction "2_3.B") (pintype "bidirectional"))
      (node (ref "B1") (pin "4.B") (pinfunction "2_4.B") (pintype "bidirectional"))
      (node (ref "C4") (pin "2") (pinfunction "+_2") (pintype "passive"))
      (node (ref "R4") (pin "2") (pinfunction "2_2") (pintype "passive"))
      (node (ref "U3") (pin "10") (pinfunction "10.RB7_10") (pintype "bidirectional"))
      (node (ref "U5") (pin "10.L") (pinfunction "10_10.L") (pintype "bidirectional"))
      (node (ref "U5") (pin "10.R") (pinfunction "10_10.R") (pintype "bidirectional"))
    )
    (net (code "44") (name "RC0") (class "Default")
      (node (ref "U1") (pin "4") (pinfunction "4_4") (pintype "bidirectional"))
      (node (ref "U3") (pin "16") (pinfunction "16.RC0_16") (pintype "bidirectional"))
      (node (ref "U5") (pin "16.L") (pinfunction "16_16.L") (pintype "bidirectional"))
      (node (ref "U5") (pin "16.R") (pinfunction "16_16.R") (pintype "bidirectional"))
    )
    (net (code "45") (name "RC1") (class "Default")
      (node (ref "U1") (pin "3") (pinfunction "3_3") (pintype "bidirectional"))
      (node (ref "U3") (pin "15") (pinfunction "15.RC1_15") (pintype "bidirectional"))
      (node (ref "U5") (pin "15.L") (pinfunction "15_15.L") (pintype "bidirectional"))
      (node (ref "U5") (pin "15.R") (pinfunction "15_15.R") (pintype "bidirectional"))
    )
    (net (code "46") (name "RC2") (class "Default")
      (node (ref "J5") (pin "3") (pinfunction "3.ADC0_3") (pintype "bidirectional"))
      (node (ref "U3") (pin "14") (pinfunction "14.RC2_14") (pintype "bidirectional"))
      (node (ref "U5") (pin "14.L") (pinfunction "14_14.L") (pintype "bidirectional"))
      (node (ref "U5") (pin "14.R") (pinfunction "14_14.R") (pintype "bidirectional"))
    )
    (net (code "47") (name "RC3") (class "Default")
      (node (ref "J5") (pin "4") (pinfunction "4.ADC1_4") (pintype "bidirectional"))
      (node (ref "U3") (pin "7") (pinfunction "7.RC3_7") (pintype "bidirectional"))
      (node (ref "U5") (pin "7.L") (pinfunction "7_7.L") (pintype "bidirectional"))
      (node (ref "U5") (pin "7.R") (pinfunction "7_7.R") (pintype "bidirectional"))
    )
    (net (code "48") (name "RC4") (class "Default")
      (node (ref "U2") (pin "3.RXI") (pinfunction "(3)MCU.TX_3.RXI") (pintype "bidirectional"))
      (node (ref "U3") (pin "6") (pinfunction "6.RC4_6") (pintype "bidirectional"))
      (node (ref "U5") (pin "6.L") (pinfunction "6_6.L") (pintype "bidirectional"))
      (node (ref "U5") (pin "6.R") (pinfunction "6_6.R") (pintype "bidirectional"))
    )
    (net (code "49") (name "RC5") (class "Default")
      (node (ref "U2") (pin "4.RDO") (pinfunction "(4)MCU.RX_4.RDO") (pintype "bidirectional"))
      (node (ref "U3") (pin "5") (pinfunction "5.RC5_5") (pintype "bidirectional"))
      (node (ref "U5") (pin "5.L") (pinfunction "5_5.L") (pintype "bidirectional"))
      (node (ref "U5") (pin "5.R") (pinfunction "5_5.R") (pintype "bidirectional"))
    )
    (net (code "50") (name "RC6") (class "Default")
      (node (ref "R1") (pin "1") (pinfunction "1_1") (pintype "passive"))
      (node (ref "U3") (pin "8") (pinfunction "8.RC6_8") (pintype "bidirectional"))
      (node (ref "U5") (pin "8.L") (pinfunction "8_8.L") (pintype "bidirectional"))
      (node (ref "U5") (pin "8.R") (pinfunction "8_8.R") (pintype "bidirectional"))
    )
    (net (code "51") (name "RC7") (class "Default")
      (node (ref "U1") (pin "2") (pinfunction "2_2") (pintype "bidirectional"))
      (node (ref "U3") (pin "9") (pinfunction "9.RC7_9") (pintype "bidirectional"))
      (node (ref "U5") (pin "9.L") (pinfunction "9_9.L") (pintype "bidirectional"))
      (node (ref "U5") (pin "9.R") (pinfunction "9_9.R") (pintype "bidirectional"))
    )
    (net (code "52") (name "SCL") (class "Default")
      (node (ref "J8-") (pin "5") (pinfunction "1_5") (pintype "bidirectional"))
      (node (ref "R6") (pin "2") (pinfunction "2_2") (pintype "passive"))
      (node (ref "U$3") (pin "3.SCL") (pinfunction "3.SCL_3.SCL") (pintype "bidirectional"))
      (node (ref "U3") (pin "11") (pinfunction "11.RB6_11") (pintype "bidirectional"))
      (node (ref "U4") (pin "4") (pinfunction "4.SCL_4") (pintype "bidirectional"))
      (node (ref "U5") (pin "11.L") (pinfunction "11_11.L") (pintype "bidirectional"))
      (node (ref "U5") (pin "11.R") (pinfunction "11_11.R") (pintype "bidirectional"))
      (node (ref "U6") (pin "28") (pinfunction "PC5_28") (pintype "bidirectional"))
    )
    (net (code "53") (name "SDA") (class "Default")
      (node (ref "J8-") (pin "3") (pinfunction "1_3") (pintype "bidirectional"))
      (node (ref "R5") (pin "2") (pinfunction "2_2") (pintype "passive"))
      (node (ref "U$3") (pin "4.SDA") (pinfunction "4.SDA_4.SDA") (pintype "bidirectional"))
      (node (ref "U3") (pin "13") (pinfunction "13.RB4_13") (pintype "bidirectional"))
      (node (ref "U4") (pin "3") (pinfunction "3.SDA_3") (pintype "bidirectional"))
      (node (ref "U5") (pin "13.L") (pinfunction "13_13.L") (pintype "bidirectional"))
      (node (ref "U5") (pin "13.R") (pinfunction "13_13.R") (pintype "bidirectional"))
      (node (ref "U6") (pin "27") (pinfunction "PC4_27") (pintype "bidirectional"))
    )
    (net (code "54") (name "VDD") (class "Default")
      (node (ref "C1") (pin "2") (pinfunction "+_2") (pintype "passive"))
      (node (ref "C12") (pin "2") (pinfunction "+_2") (pintype "passive"))
      (node (ref "C13") (pin "2") (pinfunction "+_2") (pintype "passive"))
      (node (ref "C2") (pin "2") (pinfunction "+_2") (pintype "passive"))
      (node (ref "C3") (pin "2") (pinfunction "+_2") (pintype "passive"))
      (node (ref "C6") (pin "2") (pinfunction "+_2") (pintype "passive"))
      (node (ref "J1") (pin "2") (pinfunction "2_2") (pintype "bidirectional"))
      (node (ref "J10") (pin "2") (pinfunction "2.VDD_2") (pintype "bidirectional"))
      (node (ref "J11") (pin "2") (pinfunction "2.VDD_2") (pintype "bidirectional"))
      (node (ref "J4") (pin "2") (pinfunction "2.VDD(PWR)_2") (pintype "bidirectional"))
      (node (ref "J5") (pin "2") (pinfunction "2.VDD_2") (pintype "bidirectional"))
      (node (ref "J6") (pin "2") (pinfunction "2_2") (pintype "bidirectional"))
      (node (ref "J9") (pin "2") (pinfunction "2.VDD_2") (pintype "bidirectional"))
      (node (ref "LED1") (pin "4") (pinfunction "3.+_4") (pintype "passive"))
      (node (ref "R10") (pin "1") (pinfunction "1_1") (pintype "passive"))
      (node (ref "R11") (pin "1") (pinfunction "1_1") (pintype "passive"))
      (node (ref "R15") (pin "1") (pinfunction "1_1") (pintype "passive"))
      (node (ref "R4") (pin "1") (pinfunction "1_1") (pintype "passive"))
      (node (ref "R5") (pin "1") (pinfunction "1_1") (pintype "passive"))
      (node (ref "R6") (pin "1") (pinfunction "1_1") (pintype "passive"))
      (node (ref "R8") (pin "1") (pinfunction "1_1") (pintype "passive"))
      (node (ref "U$3") (pin "1.VDD") (pinfunction "1.VDD_1.VDD") (pintype "bidirectional"))
      (node (ref "U3") (pin "1") (pinfunction "1.VDD_1") (pintype "bidirectional"))
      (node (ref "U4") (pin "2") (pinfunction "2.VDD_2") (pintype "bidirectional"))
      (node (ref "U5") (pin "1.L") (pinfunction "1_1.L") (pintype "bidirectional"))
      (node (ref "U5") (pin "1.R") (pinfunction "1_1.R") (pintype "bidirectional"))
      (node (ref "U6") (pin "4") (pinfunction "VCC_2_4") (pintype "power_in"))
      (node (ref "U6") (pin "6") (pinfunction "VCC_6") (pintype "power_in"))
    )
    (net (code "55") (name "XTAL1") (class "Default")
      (node (ref "C7") (pin "2") (pinfunction "+_2") (pintype "passive"))
      (node (ref "U6") (pin "7") (pinfunction "PB6_7") (pintype "bidirectional"))
      (node (ref "XTAL1") (pin "2") (pinfunction "2_2") (pintype "bidirectional"))
      (node (ref "XTAL1") (pin "4") (pinfunction "2_4") (pintype "bidirectional"))
    )
    (net (code "56") (name "XTAL2") (class "Default")
      (node (ref "C8") (pin "2") (pinfunction "+_2") (pintype "passive"))
      (node (ref "U6") (pin "8") (pinfunction "PB7_8") (pintype "bidirectional"))
      (node (ref "XTAL1") (pin "1") (pinfunction "1_1") (pintype "bidirectional"))
      (node (ref "XTAL1") (pin "3") (pinfunction "1_3") (pintype "bidirectional"))
    )
    (net (code "57") (name "unconnected-(J4-6.PGM-Pad6)") (class "Default")
      (node (ref "J4") (pin "6") (pinfunction "6.PGM_6") (pintype "bidirectional"))
    )
    (net (code "58") (name "unconnected-(J7-PadRING_SW)") (class "Default")
      (node (ref "J7") (pin "RING_SW") (pinfunction "RING_SW_RING_SW") (pintype "bidirectional"))
    )
    (net (code "59") (name "unconnected-(J8--Pad1)") (class "Default")
      (node (ref "J8-") (pin "1") (pinfunction "1_1") (pintype "bidirectional"))
    )
    (net (code "60") (name "unconnected-(J8-A-1-Pad10)") (class "Default")
      (node (ref "J8-") (pin "10") (pinfunction "1_10") (pintype "bidirectional"))
    )
    (net (code "61") (name "unconnected-(J8-AB-1-Pad35)") (class "Default")
      (node (ref "J8-") (pin "35") (pinfunction "1_35") (pintype "bidirectional"))
    )
    (net (code "62") (name "unconnected-(J8-AC-1-Pad36)") (class "Default")
      (node (ref "J8-") (pin "36") (pinfunction "1_36") (pintype "bidirectional"))
    )
    (net (code "63") (name "unconnected-(J8-AD-1-Pad37)") (class "Default")
      (node (ref "J8-") (pin "37") (pinfunction "1_37") (pintype "bidirectional"))
    )
    (net (code "64") (name "unconnected-(J8-AE-1-Pad38)") (class "Default")
      (node (ref "J8-") (pin "38") (pinfunction "1_38") (pintype "bidirectional"))
    )
    (net (code "65") (name "unconnected-(J8-AH-1-Pad40)") (class "Default")
      (node (ref "J8-") (pin "40") (pinfunction "1_40") (pintype "bidirectional"))
    )
    (net (code "66") (name "unconnected-(J8-AL-1-Pad7)") (class "Default")
      (node (ref "J8-") (pin "7") (pinfunction "1_7") (pintype "bidirectional"))
    )
    (net (code "67") (name "unconnected-(J8-AM-1-Pad8)") (class "Default")
      (node (ref "J8-") (pin "8") (pinfunction "1_8") (pintype "bidirectional"))
    )
    (net (code "68") (name "unconnected-(J8-B-1-Pad11)") (class "Default")
      (node (ref "J8-") (pin "11") (pinfunction "1_11") (pintype "bidirectional"))
    )
    (net (code "69") (name "unconnected-(J8-C-1-Pad12)") (class "Default")
      (node (ref "J8-") (pin "12") (pinfunction "1_12") (pintype "bidirectional"))
    )
    (net (code "70") (name "unconnected-(J8-D-1-Pad13)") (class "Default")
      (node (ref "J8-") (pin "13") (pinfunction "1_13") (pintype "bidirectional"))
    )
    (net (code "71") (name "unconnected-(J8-F-1-Pad15)") (class "Default")
      (node (ref "J8-") (pin "15") (pinfunction "1_15") (pintype "bidirectional"))
    )
    (net (code "72") (name "unconnected-(J8-G-1-Pad16)") (class "Default")
      (node (ref "J8-") (pin "16") (pinfunction "1_16") (pintype "bidirectional"))
    )
    (net (code "73") (name "unconnected-(J8-H-1-Pad17)") (class "Default")
      (node (ref "J8-") (pin "17") (pinfunction "1_17") (pintype "bidirectional"))
    )
    (net (code "74") (name "unconnected-(J8-I-1-Pad18)") (class "Default")
      (node (ref "J8-") (pin "18") (pinfunction "1_18") (pintype "bidirectional"))
    )
    (net (code "75") (name "unconnected-(J8-J-1-Pad19)") (class "Default")
      (node (ref "J8-") (pin "19") (pinfunction "1_19") (pintype "bidirectional"))
    )
    (net (code "76") (name "unconnected-(J8-M-1-Pad21)") (class "Default")
      (node (ref "J8-") (pin "21") (pinfunction "1_21") (pintype "bidirectional"))
    )
    (net (code "77") (name "unconnected-(J8-N-1-Pad22)") (class "Default")
      (node (ref "J8-") (pin "22") (pinfunction "1_22") (pintype "bidirectional"))
    )
    (net (code "78") (name "unconnected-(J8-O-1-Pad23)") (class "Default")
      (node (ref "J8-") (pin "23") (pinfunction "1_23") (pintype "bidirectional"))
    )
    (net (code "79") (name "unconnected-(J8-P-1-Pad24)") (class "Default")
      (node (ref "J8-") (pin "24") (pinfunction "1_24") (pintype "bidirectional"))
    )
    (net (code "80") (name "unconnected-(J8-R-1-Pad26)") (class "Default")
      (node (ref "J8-") (pin "26") (pinfunction "1_26") (pintype "bidirectional"))
    )
    (net (code "81") (name "unconnected-(J8-S-1-Pad27)") (class "Default")
      (node (ref "J8-") (pin "27") (pinfunction "1_27") (pintype "bidirectional"))
    )
    (net (code "82") (name "unconnected-(J8-T-1-Pad28)") (class "Default")
      (node (ref "J8-") (pin "28") (pinfunction "1_28") (pintype "bidirectional"))
    )
    (net (code "83") (name "unconnected-(J8-U-1-Pad29)") (class "Default")
      (node (ref "J8-") (pin "29") (pinfunction "1_29") (pintype "bidirectional"))
    )
    (net (code "84") (name "unconnected-(J8-X-1-Pad31)") (class "Default")
      (node (ref "J8-") (pin "31") (pinfunction "1_31") (pintype "bidirectional"))
    )
    (net (code "85") (name "unconnected-(J8-Y-1-Pad32)") (class "Default")
      (node (ref "J8-") (pin "32") (pinfunction "1_32") (pintype "bidirectional"))
    )
    (net (code "86") (name "unconnected-(J8-Z-1-Pad33)") (class "Default")
      (node (ref "J8-") (pin "33") (pinfunction "1_33") (pintype "bidirectional"))
    )
    (net (code "87") (name "unconnected-(U2-(1)3V3-Pad1.3V3)") (class "Default")
      (node (ref "U2") (pin "1.3V3") (pinfunction "(1)3V3_1.3V3") (pintype "bidirectional"))
    )
    (net (code "88") (name "unconnected-(U2-(2)DTR-Pad2.DTR)") (class "Default")
      (node (ref "U2") (pin "2.DTR") (pinfunction "(2)DTR_2.DTR") (pintype "bidirectional"))
    )
    (net (code "89") (name "unconnected-(U7-(1)3V3-Pad1.3V3)") (class "Default")
      (node (ref "U7") (pin "1.3V3") (pinfunction "(1)3V3_1.3V3") (pintype "bidirectional"))
    )
    (net (code "90") (name "unconnected-(U7-(2)DTR-Pad2.DTR)") (class "Default")
      (node (ref "U7") (pin "2.DTR") (pinfunction "(2)DTR_2.DTR") (pintype "bidirectional"))
    )
  )
)
